# pots.net
KiCad netlist of a schematic drawn in EAGLE
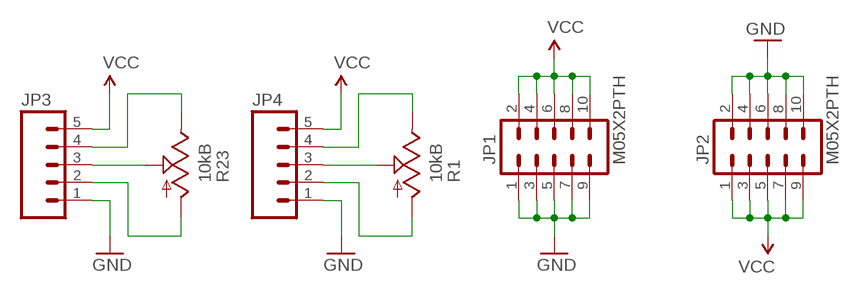
[diagram p0: schematic, sheet 1]

(export (version "E")
  (design (tool "Eeschema 10.0.6"))
  (components
    (comp (ref "JP1")
      (value "M05X2PTH")
      (footprint "eagle-import:AVR_ICSP")
      (libsource (lib "eagle-import") (part "M05X2PTH"))
    )
    (comp (ref "JP2")
      (value "M05X2PTH")
      (footprint "eagle-import:AVR_ICSP")
      (libsource (lib "eagle-import") (part "M05X2PTH"))
    )
    (comp (ref "JP3")
      (value "M05PTH")
      (footprint "eagle-import:1X05")
      (libsource (lib "eagle-import") (part "M05PTH"))
    )
    (comp (ref "JP4")
      (value "M05PTH")
      (footprint "eagle-import:1X05")
      (libsource (lib "eagle-import") (part "M05PTH"))
    )
    (comp (ref "R1")
      (value "10kB")
      (footprint "eagle-import:ALPS_POT_VERTICAL")
      (libsource (lib "eagle-import") (part "POT_USVERTICAL"))
    )
    (comp (ref "R23")
      (value "10kB")
      (footprint "eagle-import:ALPS_POT_VERTICAL")
      (libsource (lib "eagle-import") (part "POT_USVERTICAL"))
    )
  )
  (nets
    (net (code "1") (name "GND") (class "Default")
      (node (ref "JP1") (pin "1") (pinfunction "1_1") (pintype "passive"))
      (node (ref "JP1") (pin "3") (pinfunction "3_3") (pintype "passive"))
      (node (ref "JP1") (pin "5") (pinfunction "5_5") (pintype "passive"))
      (node (ref "JP1") (pin "7") (pinfunction "7_7") (pintype "passive"))
      (node (ref "JP1") (pin "9") (pinfunction "9_9") (pintype "passive"))
      (node (ref "JP2") (pin "10") (pinfunction "10_10") (pintype "passive"))
      (node (ref "JP2") (pin "2") (pinfunction "2_2") (pintype "passive"))
      (node (ref "JP2") (pin "4") (pinfunction "4_4") (pintype "passive"))
      (node (ref "JP2") (pin "6") (pinfunction "6_6") (pintype "passive"))
      (node (ref "JP2") (pin "8") (pinfunction "8_8") (pintype "passive"))
      (node (ref "JP3") (pin "1") (pinfunction "1_1") (pintype "passive"))
      (node (ref "JP4") (pin "1") (pinfunction "1_1") (pintype "passive"))
    )
    (net (code "2") (name "Net-(R1-A)") (class "Default")
      (node (ref "JP4") (pin "2") (pinfunction "2_2") (pintype "passive"))
      (node (ref "R1") (pin "P$3") (pinfunction "A_P$3") (pintype "passive"))
    )
    (net (code "3") (name "Net-(R1-E)") (class "Default")
      (node (ref "JP4") (pin "4") (pinfunction "4_4") (pintype "passive"))
      (node (ref "R1") (pin "P$1") (pinfunction "E_P$1") (pintype "passive"))
    )
    (net (code "4") (name "Net-(R1-S)") (class "Default")
      (node (ref "JP4") (pin "3") (pinfunction "3_3") (pintype "passive"))
      (node (ref "R1") (pin "P$2") (pinfunction "S_P$2") (pintype "passive"))
    )
    (net (code "5") (name "Net-(R23-A)") (class "Default")
      (node (ref "JP3") (pin "2") (pinfunction "2_2") (pintype "passive"))
      (node (ref "R23") (pin "P$3") (pinfunction "A_P$3") (pintype "passive"))
    )
    (net (code "6") (name "Net-(R23-E)") (class "Default")
      (node (ref "JP3") (pin "4") (pinfunction "4_4") (pintype "passive"))
      (node (ref "R23") (pin "P$1") (pinfunction "E_P$1") (pintype "passive"))
    )
    (net (code "7") (name "Net-(R23-S)") (class "Default")
      (node (ref "JP3") (pin "3") (pinfunction "3_3") (pintype "passive"))
      (node (ref "R23") (pin "P$2") (pinfunction "S_P$2") (pintype "passive"))
    )
    (net (code "8") (name "VCC") (class "Default")
      (node (ref "JP1") (pin "10") (pinfunction "10_10") (pintype "passive"))
      (node (ref "JP1") (pin "2") (pinfunction "2_2") (pintype "passive"))
      (node (ref "JP1") (pin "4") (pinfunction "4_4") (pintype "passive"))
      (node (ref "JP1") (pin "6") (pinfunction "6_6") (pintype "passive"))
      (node (ref "JP1") (pin "8") (pinfunction "8_8") (pintype "passive"))
      (node (ref "JP2") (pin "1") (pinfunction "1_1") (pintype "passive"))
      (node (ref "JP2") (pin "3") (pinfunction "3_3") (pintype "passive"))
      (node (ref "JP2") (pin "5") (pinfunction "5_5") (pintype "passive"))
      (node (ref "JP2") (pin "7") (pinfunction "7_7") (pintype "passive"))
      (node (ref "JP2") (pin "9") (pinfunction "9_9") (pintype "passive"))
      (node (ref "JP3") (pin "5") (pinfunction "5_5") (pintype "passive"))
      (node (ref "JP4") (pin "5") (pinfunction "5_5") (pintype "passive"))
    )
  )
)
